# Sheet4.net
KiCad netlist of a schematic drawn in Altium Designer
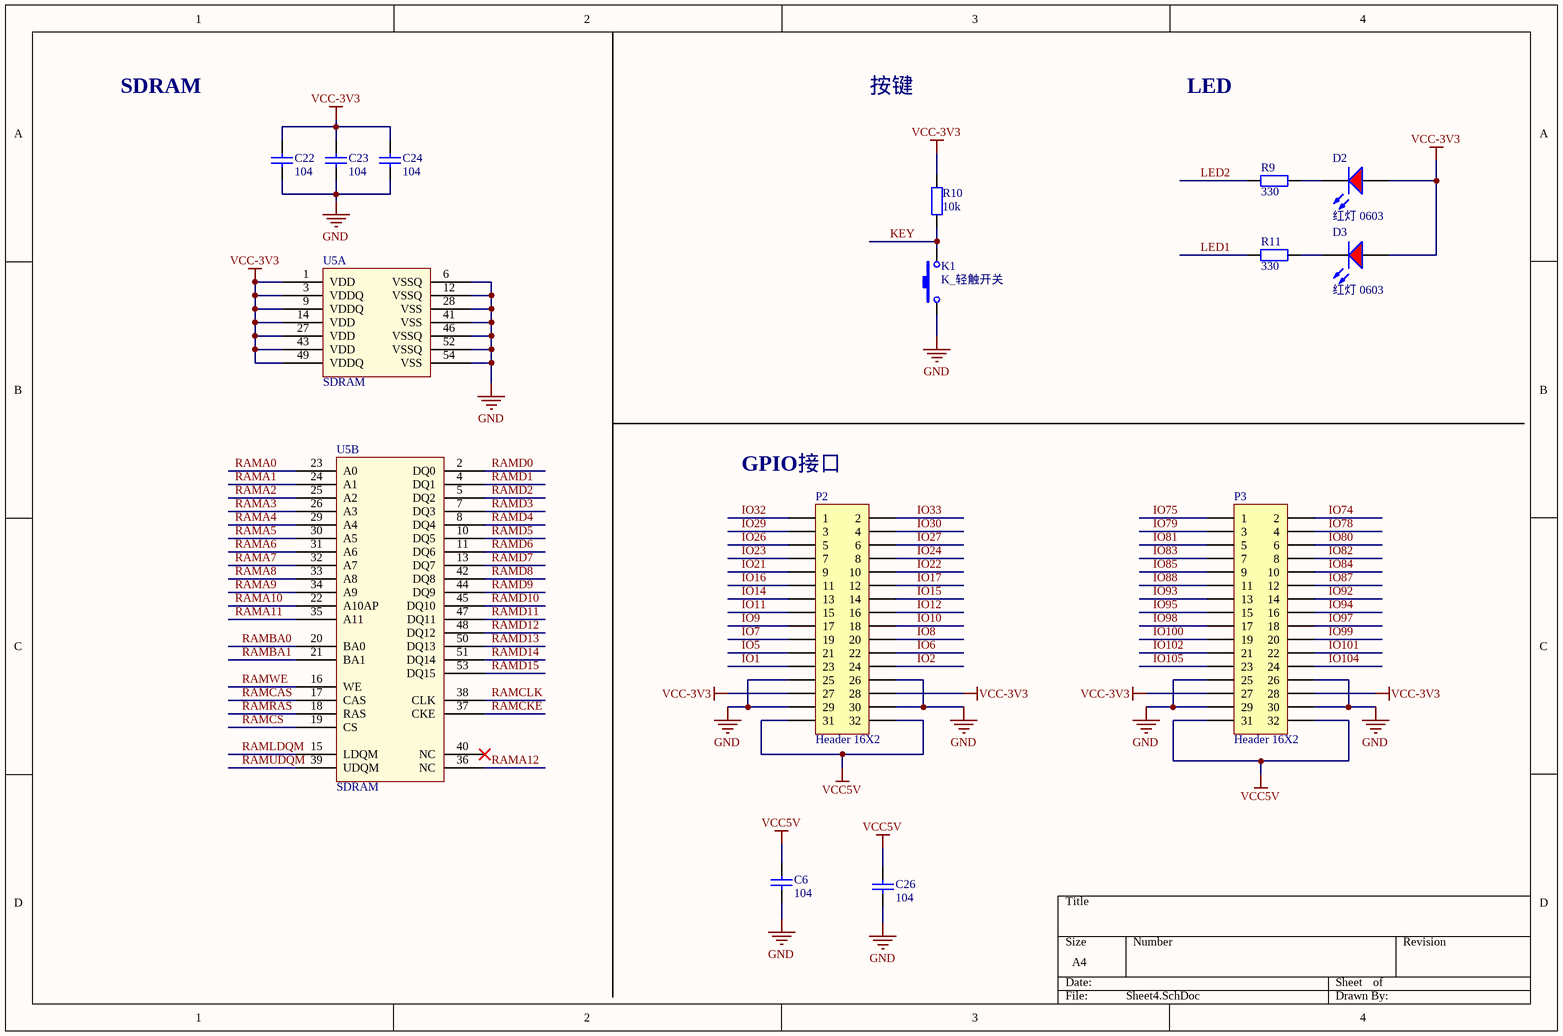
[diagram p0: Sheet4.SchDoc]

(export (version "E")
  (design (tool "Eeschema 10.0.6"))
  (components
    (comp (ref "C6")
      (value "104")
      (footprint "0603_C")
      (description "贴片电容")
      (libsource (lib "Cap") (part "0603 30pF (300) 5% 50V"))
    )
    (comp (ref "C22")
      (value "104")
      (footprint "0603_C")
      (description "贴片电容")
      (libsource (lib "Cap") (part "0603 30pF (300) 5% 50V"))
    )
    (comp (ref "C23")
      (value "104")
      (footprint "0603_C")
      (description "贴片电容")
      (libsource (lib "Cap") (part "0603 30pF (300) 5% 50V"))
    )
    (comp (ref "C24")
      (value "104")
      (footprint "0603_C")
      (description "贴片电容")
      (libsource (lib "Cap") (part "0603 30pF (300) 5% 50V"))
    )
    (comp (ref "C26")
      (value "104")
      (footprint "0603_C")
      (description "贴片电容")
      (libsource (lib "Cap") (part "0603 30pF (300) 5% 50V"))
    )
    (comp (ref "D2")
      (value "红灯 0603")
      (footprint "0603_LED_S1")
      (description "发光二极管")
      (libsource (lib "LED") (part "0603 红灯"))
    )
    (comp (ref "D3")
      (value "红灯 0603")
      (footprint "0603_LED_S1")
      (description "发光二极管")
      (libsource (lib "LED") (part "0603 红灯"))
    )
    (comp (ref "K1") (value "K_轻触开关") (footprint "KEY") (libsource (lib "集成库") (part "K_轻触开关")))
    (comp (ref "P2")
      (value "Header 16X2")
      (footprint "HDR2X16")
      (description "Header, 16-Pin, Dual row")
      (fields (field (name "PUBLISHER") "Altium Limited"))
      (libsource (lib "Miscellaneous Connectors") (part "Header 16X2"))
    )
    (comp (ref "P3")
      (value "Header 16X2")
      (footprint "HDR2X16")
      (description "Header, 16-Pin, Dual row")
      (fields (field (name "PUBLISHER") "Altium Limited"))
      (libsource (lib "Miscellaneous Connectors") (part "Header 16X2"))
    )
    (comp (ref "R9")
      (value "330")
      (footprint "0603_R")
      (description "贴片电阻")
      (libsource (lib "") (part "0603 9.1KΩ (9101) 1%_1"))
    )
    (comp (ref "R10")
      (value "10k")
      (footprint "0603_R")
      (description "贴片电阻")
      (libsource (lib "RES") (part "0603 9.1KΩ (9101) 1%"))
    )
    (comp (ref "R11")
      (value "330")
      (footprint "0603_R")
      (description "贴片电阻")
      (libsource (lib "") (part "0603 9.1KΩ (9101) 1%_1"))
    )
    (comp (ref "U5") (value "SDRAM") (footprint "SDRAM") (libsource (lib "FPGA_EX") (part "SDRAM")))
  )
  (nets
    (net (code "1") (name "/IO1") (class "Default")
      (node (ref "P2") (pin "23") (pinfunction "23_23") (pintype "passive"))
    )
    (net (code "2") (name "/IO2") (class "Default")
      (node (ref "P2") (pin "24") (pinfunction "24_24") (pintype "passive"))
    )
    (net (code "3") (name "/IO5") (class "Default")
      (node (ref "P2") (pin "21") (pinfunction "21_21") (pintype "passive"))
    )
    (net (code "4") (name "/IO6") (class "Default")
      (node (ref "P2") (pin "22") (pinfunction "22_22") (pintype "passive"))
    )
    (net (code "5") (name "/IO7") (class "Default")
      (node (ref "P2") (pin "19") (pinfunction "19_19") (pintype "passive"))
    )
    (net (code "6") (name "/IO8") (class "Default")
      (node (ref "P2") (pin "20") (pinfunction "20_20") (pintype "passive"))
    )
    (net (code "7") (name "/IO9") (class "Default")
      (node (ref "P2") (pin "17") (pinfunction "17_17") (pintype "passive"))
    )
    (net (code "8") (name "/IO10") (class "Default")
      (node (ref "P2") (pin "18") (pinfunction "18_18") (pintype "passive"))
    )
    (net (code "9") (name "/IO11") (class "Default")
      (node (ref "P2") (pin "15") (pinfunction "15_15") (pintype "passive"))
    )
    (net (code "10") (name "/IO12") (class "Default")
      (node (ref "P2") (pin "16") (pinfunction "16_16") (pintype "passive"))
    )
    (net (code "11") (name "/IO14") (class "Default")
      (node (ref "P2") (pin "13") (pinfunction "13_13") (pintype "passive"))
    )
    (net (code "12") (name "/IO15") (class "Default")
      (node (ref "P2") (pin "14") (pinfunction "14_14") (pintype "passive"))
    )
    (net (code "13") (name "/IO16") (class "Default")
      (node (ref "P2") (pin "11") (pinfunction "11_11") (pintype "passive"))
    )
    (net (code "14") (name "/IO17") (class "Default")
      (node (ref "P2") (pin "12") (pinfunction "12_12") (pintype "passive"))
    )
    (net (code "15") (name "/IO21") (class "Default")
      (node (ref "P2") (pin "9") (pinfunction "9_9") (pintype "passive"))
    )
    (net (code "16") (name "/IO22") (class "Default")
      (node (ref "P2") (pin "10") (pinfunction "10_10") (pintype "passive"))
    )
    (net (code "17") (name "/IO23") (class "Default")
      (node (ref "P2") (pin "7") (pinfunction "7_7") (pintype "passive"))
    )
    (net (code "18") (name "/IO24") (class "Default")
      (node (ref "P2") (pin "8") (pinfunction "8_8") (pintype "passive"))
    )
    (net (code "19") (name "/IO26") (class "Default")
      (node (ref "P2") (pin "5") (pinfunction "5_5") (pintype "passive"))
    )
    (net (code "20") (name "/IO27") (class "Default")
      (node (ref "P2") (pin "6") (pinfunction "6_6") (pintype "passive"))
    )
    (net (code "21") (name "/IO29") (class "Default")
      (node (ref "P2") (pin "3") (pinfunction "3_3") (pintype "passive"))
    )
    (net (code "22") (name "/IO30") (class "Default")
      (node (ref "P2") (pin "4") (pinfunction "4_4") (pintype "passive"))
    )
    (net (code "23") (name "/IO32") (class "Default")
      (node (ref "P2") (pin "1") (pinfunction "1_1") (pintype "passive"))
    )
    (net (code "24") (name "/IO33") (class "Default")
      (node (ref "P2") (pin "2") (pinfunction "2_2") (pintype "passive"))
    )
    (net (code "25") (name "/IO74") (class "Default")
      (node (ref "P3") (pin "2") (pinfunction "2_2") (pintype "passive"))
    )
    (net (code "26") (name "/IO75") (class "Default")
      (node (ref "P3") (pin "1") (pinfunction "1_1") (pintype "passive"))
    )
    (net (code "27") (name "/IO78") (class "Default")
      (node (ref "P3") (pin "4") (pinfunction "4_4") (pintype "passive"))
    )
    (net (code "28") (name "/IO79") (class "Default")
      (node (ref "P3") (pin "3") (pinfunction "3_3") (pintype "passive"))
    )
    (net (code "29") (name "/IO80") (class "Default")
      (node (ref "P3") (pin "6") (pinfunction "6_6") (pintype "passive"))
    )
    (net (code "30") (name "/IO81") (class "Default")
      (node (ref "P3") (pin "5") (pinfunction "5_5") (pintype "passive"))
    )
    (net (code "31") (name "/IO82") (class "Default")
      (node (ref "P3") (pin "8") (pinfunction "8_8") (pintype "passive"))
    )
    (net (code "32") (name "/IO83") (class "Default")
      (node (ref "P3") (pin "7") (pinfunction "7_7") (pintype "passive"))
    )
    (net (code "33") (name "/IO84") (class "Default")
      (node (ref "P3") (pin "10") (pinfunction "10_10") (pintype "passive"))
    )
    (net (code "34") (name "/IO85") (class "Default")
      (node (ref "P3") (pin "9") (pinfunction "9_9") (pintype "passive"))
    )
    (net (code "35") (name "/IO87") (class "Default")
      (node (ref "P3") (pin "12") (pinfunction "12_12") (pintype "passive"))
    )
    (net (code "36") (name "/IO88") (class "Default")
      (node (ref "P3") (pin "11") (pinfunction "11_11") (pintype "passive"))
    )
    (net (code "37") (name "/IO92") (class "Default")
      (node (ref "P3") (pin "14") (pinfunction "14_14") (pintype "passive"))
    )
    (net (code "38") (name "/IO93") (class "Default")
      (node (ref "P3") (pin "13") (pinfunction "13_13") (pintype "passive"))
    )
    (net (code "39") (name "/IO94") (class "Default")
      (node (ref "P3") (pin "16") (pinfunction "16_16") (pintype "passive"))
    )
    (net (code "40") (name "/IO95") (class "Default")
      (node (ref "P3") (pin "15") (pinfunction "15_15") (pintype "passive"))
    )
    (net (code "41") (name "/IO97") (class "Default")
      (node (ref "P3") (pin "18") (pinfunction "18_18") (pintype "passive"))
    )
    (net (code "42") (name "/IO98") (class "Default")
      (node (ref "P3") (pin "17") (pinfunction "17_17") (pintype "passive"))
    )
    (net (code "43") (name "/IO99") (class "Default")
      (node (ref "P3") (pin "20") (pinfunction "20_20") (pintype "passive"))
    )
    (net (code "44") (name "/IO100") (class "Default")
      (node (ref "P3") (pin "19") (pinfunction "19_19") (pintype "passive"))
    )
    (net (code "45") (name "/IO101") (class "Default")
      (node (ref "P3") (pin "22") (pinfunction "22_22") (pintype "passive"))
    )
    (net (code "46") (name "/IO102") (class "Default")
      (node (ref "P3") (pin "21") (pinfunction "21_21") (pintype "passive"))
    )
    (net (code "47") (name "/IO104") (class "Default")
      (node (ref "P3") (pin "24") (pinfunction "24_24") (pintype "passive"))
    )
    (net (code "48") (name "/IO105") (class "Default")
      (node (ref "P3") (pin "23") (pinfunction "23_23") (pintype "passive"))
    )
    (net (code "49") (name "/KEY") (class "Default")
      (node (ref "K1") (pin "2") (pinfunction "2_2") (pintype "passive"))
      (node (ref "R10") (pin "2") (pinfunction "2_2") (pintype "passive"))
    )
    (net (code "50") (name "/LED1") (class "Default")
      (node (ref "R11") (pin "2") (pinfunction "2_2") (pintype "passive"))
    )
    (net (code "51") (name "/LED2") (class "Default")
      (node (ref "R9") (pin "2") (pinfunction "2_2") (pintype "passive"))
    )
    (net (code "52") (name "/RAMA0") (class "Default")
      (node (ref "U5") (pin "23") (pinfunction "A0_23") (pintype "passive"))
    )
    (net (code "53") (name "/RAMA1") (class "Default")
      (node (ref "U5") (pin "24") (pinfunction "A1_24") (pintype "passive"))
    )
    (net (code "54") (name "/RAMA2") (class "Default")
      (node (ref "U5") (pin "25") (pinfunction "A2_25") (pintype "passive"))
    )
    (net (code "55") (name "/RAMA3") (class "Default")
      (node (ref "U5") (pin "26") (pinfunction "A3_26") (pintype "passive"))
    )
    (net (code "56") (name "/RAMA4") (class "Default")
      (node (ref "U5") (pin "29") (pinfunction "A4_29") (pintype "passive"))
    )
    (net (code "57") (name "/RAMA5") (class "Default")
      (node (ref "U5") (pin "30") (pinfunction "A5_30") (pintype "passive"))
    )
    (net (code "58") (name "/RAMA6") (class "Default")
      (node (ref "U5") (pin "31") (pinfunction "A6_31") (pintype "passive"))
    )
    (net (code "59") (name "/RAMA7") (class "Default")
      (node (ref "U5") (pin "32") (pinfunction "A7_32") (pintype "passive"))
    )
    (net (code "60") (name "/RAMA8") (class "Default")
      (node (ref "U5") (pin "33") (pinfunction "A8_33") (pintype "passive"))
    )
    (net (code "61") (name "/RAMA9") (class "Default")
      (node (ref "U5") (pin "34") (pinfunction "A9_34") (pintype "passive"))
    )
    (net (code "62") (name "/RAMA10") (class "Default")
      (node (ref "U5") (pin "22") (pinfunction "A10AP_22") (pintype "passive"))
    )
    (net (code "63") (name "/RAMA11") (class "Default")
      (node (ref "U5") (pin "35") (pinfunction "A11_35") (pintype "passive"))
    )
    (net (code "64") (name "/RAMA12") (class "Default")
      (node (ref "U5") (pin "36") (pinfunction "NC_36") (pintype "passive"))
    )
    (net (code "65") (name "/RAMBA0") (class "Default")
      (node (ref "U5") (pin "20") (pinfunction "BA0_20") (pintype "passive"))
    )
    (net (code "66") (name "/RAMBA1") (class "Default")
      (node (ref "U5") (pin "21") (pinfunction "BA1_21") (pintype "passive"))
    )
    (net (code "67") (name "/RAMCAS") (class "Default")
      (node (ref "U5") (pin "17") (pinfunction "CAS_17") (pintype "passive"))
    )
    (net (code "68") (name "/RAMCKE") (class "Default")
      (node (ref "U5") (pin "37") (pinfunction "CKE_37") (pintype "passive"))
    )
    (net (code "69") (name "/RAMCLK") (class "Default")
      (node (ref "U5") (pin "38") (pinfunction "CLK_38") (pintype "passive"))
    )
    (net (code "70") (name "/RAMCS") (class "Default")
      (node (ref "U5") (pin "19") (pinfunction "CS_19") (pintype "passive"))
    )
    (net (code "71") (name "/RAMD0") (class "Default")
      (node (ref "U5") (pin "2") (pinfunction "DQ0_2") (pintype "passive"))
    )
    (net (code "72") (name "/RAMD1") (class "Default")
      (node (ref "U5") (pin "4") (pinfunction "DQ1_4") (pintype "passive"))
    )
    (net (code "73") (name "/RAMD2") (class "Default")
      (node (ref "U5") (pin "5") (pinfunction "DQ2_5") (pintype "passive"))
    )
    (net (code "74") (name "/RAMD3") (class "Default")
      (node (ref "U5") (pin "7") (pinfunction "DQ3_7") (pintype "passive"))
    )
    (net (code "75") (name "/RAMD4") (class "Default")
      (node (ref "U5") (pin "8") (pinfunction "DQ4_8") (pintype "passive"))
    )
    (net (code "76") (name "/RAMD5") (class "Default")
      (node (ref "U5") (pin "10") (pinfunction "DQ5_10") (pintype "passive"))
    )
    (net (code "77") (name "/RAMD6") (class "Default")
      (node (ref "U5") (pin "11") (pinfunction "DQ6_11") (pintype "passive"))
    )
    (net (code "78") (name "/RAMD7") (class "Default")
      (node (ref "U5") (pin "13") (pinfunction "DQ7_13") (pintype "passive"))
    )
    (net (code "79") (name "/RAMD8") (class "Default")
      (node (ref "U5") (pin "42") (pinfunction "DQ8_42") (pintype "passive"))
    )
    (net (code "80") (name "/RAMD9") (class "Default")
      (node (ref "U5") (pin "44") (pinfunction "DQ9_44") (pintype "passive"))
    )
    (net (code "81") (name "/RAMD10") (class "Default")
      (node (ref "U5") (pin "45") (pinfunction "DQ10_45") (pintype "passive"))
    )
    (net (code "82") (name "/RAMD11") (class "Default")
      (node (ref "U5") (pin "47") (pinfunction "DQ11_47") (pintype "passive"))
    )
    (net (code "83") (name "/RAMD12") (class "Default")
      (node (ref "U5") (pin "48") (pinfunction "DQ12_48") (pintype "passive"))
    )
    (net (code "84") (name "/RAMD13") (class "Default")
      (node (ref "U5") (pin "50") (pinfunction "DQ13_50") (pintype "passive"))
    )
    (net (code "85") (name "/RAMD14") (class "Default")
      (node (ref "U5") (pin "51") (pinfunction "DQ14_51") (pintype "passive"))
    )
    (net (code "86") (name "/RAMD15") (class "Default")
      (node (ref "U5") (pin "53") (pinfunction "DQ15_53") (pintype "passive"))
    )
    (net (code "87") (name "/RAMLDQM") (class "Default")
      (node (ref "U5") (pin "15") (pinfunction "LDQM_15") (pintype "passive"))
    )
    (net (code "88") (name "/RAMRAS") (class "Default")
      (node (ref "U5") (pin "18") (pinfunction "RAS_18") (pintype "passive"))
    )
    (net (code "89") (name "/RAMUDQM") (class "Default")
      (node (ref "U5") (pin "39") (pinfunction "UDQM_39") (pintype "passive"))
    )
    (net (code "90") (name "/RAMWE") (class "Default")
      (node (ref "U5") (pin "16") (pinfunction "WE_16") (pintype "passive"))
    )
    (net (code "91") (name "GND") (class "Default")
      (node (ref "C22") (pin "1") (pinfunction "1_1") (pintype "passive"))
      (node (ref "C23") (pin "1") (pinfunction "1_1") (pintype "passive"))
      (node (ref "C24") (pin "1") (pinfunction "1_1") (pintype "passive"))
      (node (ref "C26") (pin "1") (pinfunction "1_1") (pintype "passive"))
      (node (ref "C6") (pin "1") (pinfunction "1_1") (pintype "passive"))
      (node (ref "K1") (pin "1") (pinfunction "1_1") (pintype "passive"))
      (node (ref "P2") (pin "25") (pinfunction "25_25") (pintype "passive"))
      (node (ref "P2") (pin "26") (pinfunction "26_26") (pintype "passive"))
      (node (ref "P2") (pin "29") (pinfunction "29_29") (pintype "passive"))
      (node (ref "P2") (pin "30") (pinfunction "30_30") (pintype "passive"))
      (node (ref "P3") (pin "25") (pinfunction "25_25") (pintype "passive"))
      (node (ref "P3") (pin "26") (pinfunction "26_26") (pintype "passive"))
      (node (ref "P3") (pin "29") (pinfunction "29_29") (pintype "passive"))
      (node (ref "P3") (pin "30") (pinfunction "30_30") (pintype "passive"))
      (node (ref "U5") (pin "12") (pinfunction "VSSQ_12") (pintype "passive"))
      (node (ref "U5") (pin "28") (pinfunction "VSS_28") (pintype "passive"))
      (node (ref "U5") (pin "41") (pinfunction "VSS_41") (pintype "passive"))
      (node (ref "U5") (pin "46") (pinfunction "VSSQ_46") (pintype "passive"))
      (node (ref "U5") (pin "52") (pinfunction "VSSQ_52") (pintype "passive"))
      (node (ref "U5") (pin "54") (pinfunction "VSS_54") (pintype "passive"))
      (node (ref "U5") (pin "6") (pinfunction "VSSQ_6") (pintype "passive"))
    )
    (net (code "92") (name "Net-(D2-PadK)") (class "Default")
      (node (ref "D2") (pin "K") (pinfunction "K_K") (pintype "passive"))
      (node (ref "R9") (pin "1") (pinfunction "1_1") (pintype "passive"))
    )
    (net (code "93") (name "Net-(D3-PadK)") (class "Default")
      (node (ref "D3") (pin "K") (pinfunction "K_K") (pintype "passive"))
      (node (ref "R11") (pin "1") (pinfunction "1_1") (pintype "passive"))
    )
    (net (code "94") (name "VCC-3V3") (class "Default")
      (node (ref "C22") (pin "2") (pinfunction "2_2") (pintype "passive"))
      (node (ref "C23") (pin "2") (pinfunction "2_2") (pintype "passive"))
      (node (ref "C24") (pin "2") (pinfunction "2_2") (pintype "passive"))
      (node (ref "D2") (pin "A") (pinfunction "A_A") (pintype "passive"))
      (node (ref "D3") (pin "A") (pinfunction "A_A") (pintype "passive"))
      (node (ref "P2") (pin "27") (pinfunction "27_27") (pintype "passive"))
      (node (ref "P2") (pin "28") (pinfunction "28_28") (pintype "passive"))
      (node (ref "P3") (pin "27") (pinfunction "27_27") (pintype "passive"))
      (node (ref "P3") (pin "28") (pinfunction "28_28") (pintype "passive"))
      (node (ref "R10") (pin "1") (pinfunction "1_1") (pintype "passive"))
      (node (ref "U5") (pin "1") (pinfunction "VDD_1") (pintype "passive"))
      (node (ref "U5") (pin "14") (pinfunction "VDD_14") (pintype "passive"))
      (node (ref "U5") (pin "27") (pinfunction "VDD_27") (pintype "passive"))
      (node (ref "U5") (pin "3") (pinfunction "VDDQ_3") (pintype "passive"))
      (node (ref "U5") (pin "43") (pinfunction "VDD_43") (pintype "passive"))
      (node (ref "U5") (pin "49") (pinfunction "VDDQ_49") (pintype "passive"))
      (node (ref "U5") (pin "9") (pinfunction "VDDQ_9") (pintype "passive"))
    )
    (net (code "95") (name "VCC5V") (class "Default")
      (node (ref "C26") (pin "2") (pinfunction "2_2") (pintype "passive"))
      (node (ref "C6") (pin "2") (pinfunction "2_2") (pintype "passive"))
      (node (ref "P2") (pin "31") (pinfunction "31_31") (pintype "passive"))
      (node (ref "P2") (pin "32") (pinfunction "32_32") (pintype "passive"))
      (node (ref "P3") (pin "31") (pinfunction "31_31") (pintype "passive"))
      (node (ref "P3") (pin "32") (pinfunction "32_32") (pintype "passive"))
    )
    (net (code "96") (name "unconnected-(U5B-NC-Pad40)") (class "Default")
      (node (ref "U5") (pin "40") (pinfunction "NC_40") (pintype "passive+no_connect"))
    )
  )
)
